# MB2_B1.net
KiCad netlist of a schematic drawn in EasyEDA Pro
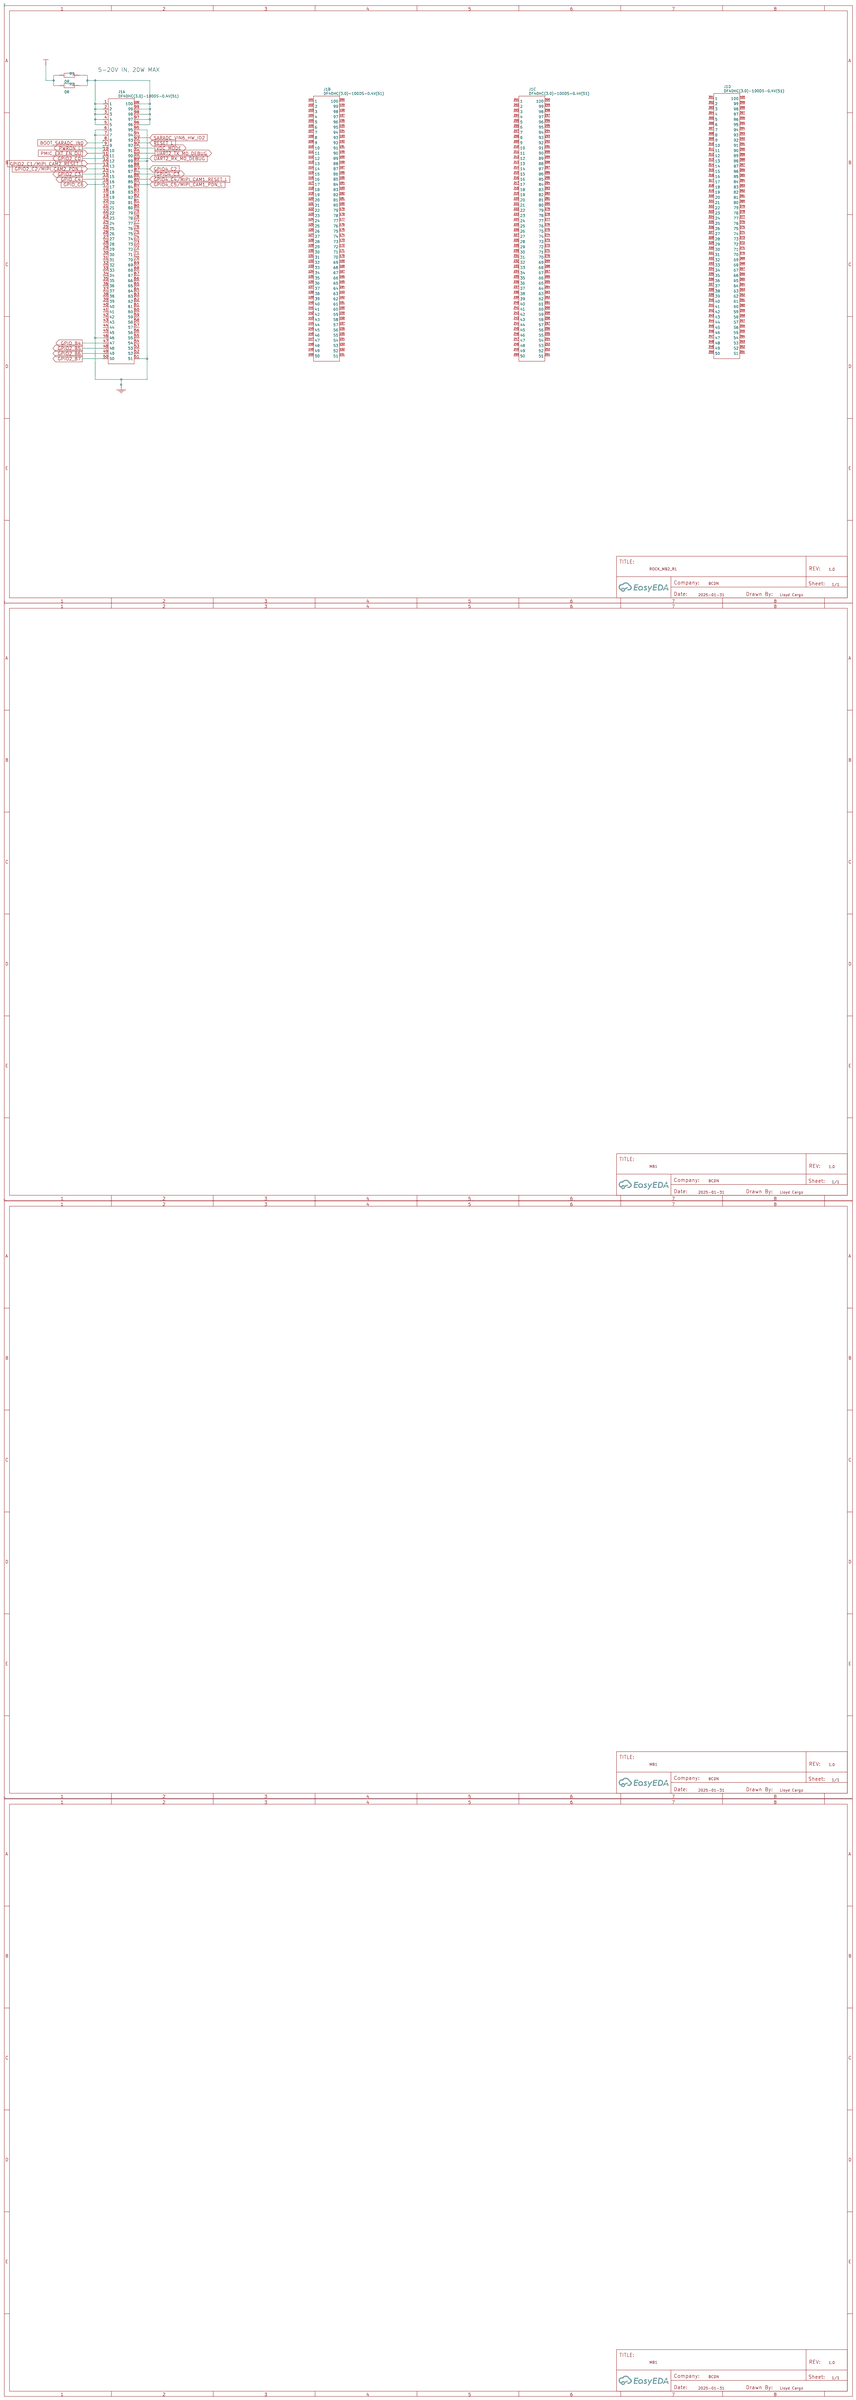
[diagram p0: schematic sheet]

(export (version "E")
  (design (tool "Eeschema 10.0.6"))
  (components
    (comp (ref "J1A")
      (value "DF40HC(3.0)-100DS-0.4V(51)")
      (fields (field (name "Manufacturer") "HRS(广濑)"))
      (libsource (lib "") (part "DF40HC(3.0)-100DS-0.4V(51)_2"))
    )
    (comp (ref "J1B")
      (value "DF40HC(3.0)-100DS-0.4V(51)")
      (fields (field (name "Manufacturer") "HRS(广濑)"))
      (libsource (lib "") (part "DF40HC(3.0)-100DS-0.4V(51)_1"))
    )
    (comp (ref "J1C")
      (value "DF40HC(3.0)-100DS-0.4V(51)")
      (fields (field (name "Manufacturer") "HRS(广濑)"))
      (libsource (lib "easyedapro") (part "DF40HC(3.0)-100DS-0.4V(51)"))
    )
    (comp (ref "J1D")
      (value "DF40HC(3.0)-100DS-0.4V(51)")
      (fields (field (name "Manufacturer") "HRS(广濑)"))
      (libsource (lib "") (part "DF40HC(3.0)-100DS-0.4V(51)_3"))
    )
    (comp (ref "R1") (value "0R") (footprint "easyedapro:R0603") (libsource (lib "easyedapro") (part "Res")))
    (comp (ref "R2") (value "0R") (footprint "easyedapro:R0603") (libsource (lib "easyedapro") (part "Res")))
  )
  (nets
    (net (code "1") (name "BOOT_SARADC_IN0") (class "Default")
      (node (ref "J1A") (pin "8") (pinfunction "8_8") (pintype "unspecified"))
    )
    (net (code "2") (name "GND") (class "Default")
      (node (ref "J1A") (pin "46") (pinfunction "46_46") (pintype "unspecified"))
      (node (ref "J1A") (pin "51") (pinfunction "51_51") (pintype "unspecified"))
      (node (ref "J1A") (pin "6") (pinfunction "6_6") (pintype "unspecified"))
      (node (ref "J1A") (pin "7") (pinfunction "7_7") (pintype "unspecified"))
      (node (ref "J1A") (pin "89") (pinfunction "89_89") (pintype "unspecified"))
      (node (ref "J1A") (pin "95") (pinfunction "95_95") (pintype "unspecified"))
    )
    (net (code "3") (name "GPIO2_B5") (class "Default")
      (node (ref "J1A") (pin "48") (pinfunction "48_48") (pintype "unspecified"))
    )
    (net (code "4") (name "GPIO2_B6") (class "Default")
      (node (ref "J1A") (pin "49") (pinfunction "49_49") (pintype "unspecified"))
    )
    (net (code "5") (name "GPIO2_B7") (class "Default")
      (node (ref "J1A") (pin "50") (pinfunction "50_50") (pintype "unspecified"))
    )
    (net (code "6") (name "GPIO2_C0") (class "Default")
      (node (ref "J1A") (pin "11") (pinfunction "11_11") (pintype "unspecified"))
    )
    (net (code "7") (name "GPIO2_C1{slash}MIPI_CAM2_RESET_L") (class "Default")
      (node (ref "J1A") (pin "12") (pinfunction "12_12") (pintype "unspecified"))
    )
    (net (code "8") (name "GPIO2_C2{slash}MIPI_CAM2_PDN_L") (class "Default")
      (node (ref "J1A") (pin "13") (pinfunction "13_13") (pintype "unspecified"))
    )
    (net (code "9") (name "GPIO2_C3") (class "Default")
      (node (ref "J1A") (pin "14") (pinfunction "14_14") (pintype "unspecified"))
    )
    (net (code "10") (name "GPIO4_C2") (class "Default")
      (node (ref "J1A") (pin "88") (pinfunction "88_88") (pintype "unspecified"))
    )
    (net (code "11") (name "GPIO4_C3") (class "Default")
      (node (ref "J1A") (pin "87") (pinfunction "87_87") (pintype "unspecified"))
    )
    (net (code "12") (name "GPIO4_C4{slash}MIPI_CAM1_RESET_L") (class "Default")
      (node (ref "J1A") (pin "86") (pinfunction "86_86") (pintype "unspecified"))
    )
    (net (code "13") (name "GPIO4_C5{slash}MIPI_CAM1_PDN_L") (class "Default")
      (node (ref "J1A") (pin "85") (pinfunction "85_85") (pintype "unspecified"))
    )
    (net (code "14") (name "GPIO_B4") (class "Default")
      (node (ref "J1A") (pin "47") (pinfunction "47_47") (pintype "unspecified"))
    )
    (net (code "15") (name "GPIO_C4") (class "Default")
      (node (ref "J1A") (pin "15") (pinfunction "15_15") (pintype "unspecified"))
    )
    (net (code "16") (name "GPIO_C6") (class "Default")
      (node (ref "J1A") (pin "16") (pinfunction "16_16") (pintype "unspecified"))
    )
    (net (code "17") (name "Net-(J1A-Pad1)") (class "Default")
      (node (ref "J1A") (pin "1") (pinfunction "1_1") (pintype "unspecified"))
      (node (ref "J1A") (pin "100") (pinfunction "100_100") (pintype "unspecified"))
      (node (ref "J1A") (pin "2") (pinfunction "2_2") (pintype "unspecified"))
      (node (ref "J1A") (pin "3") (pinfunction "3_3") (pintype "unspecified"))
      (node (ref "J1A") (pin "4") (pinfunction "4_4") (pintype "unspecified"))
      (node (ref "J1A") (pin "5") (pinfunction "5_5") (pintype "unspecified"))
      (node (ref "J1A") (pin "96") (pinfunction "96_96") (pintype "unspecified"))
      (node (ref "J1A") (pin "97") (pinfunction "97_97") (pintype "unspecified"))
      (node (ref "J1A") (pin "98") (pinfunction "98_98") (pintype "unspecified"))
      (node (ref "J1A") (pin "99") (pinfunction "99_99") (pintype "unspecified"))
      (node (ref "R1") (pin "2") (pinfunction "2_2") (pintype "input"))
      (node (ref "R2") (pin "2") (pinfunction "2_2") (pintype "input"))
    )
    (net (code "18") (name "PMIC_EXT_EN_OUT") (class "Default")
      (node (ref "J1A") (pin "10") (pinfunction "10_10") (pintype "unspecified"))
    )
    (net (code "19") (name "PWRON_L") (class "Default")
      (node (ref "J1A") (pin "9") (pinfunction "9_9") (pintype "unspecified"))
    )
    (net (code "20") (name "RESET_L") (class "Default")
      (node (ref "J1A") (pin "93") (pinfunction "93_93") (pintype "unspecified"))
    )
    (net (code "21") (name "SARADC_VIN6_HW_ID2") (class "Default")
      (node (ref "J1A") (pin "94") (pinfunction "94_94") (pintype "unspecified"))
    )
    (net (code "22") (name "UART2_RX_M0_DEBUG") (class "Default")
      (node (ref "J1A") (pin "90") (pinfunction "90_90") (pintype "unspecified"))
    )
    (net (code "23") (name "UART2_TX_M0_DEBUG") (class "Default")
      (node (ref "J1A") (pin "91") (pinfunction "91_91") (pintype "unspecified"))
    )
    (net (code "24") (name "VDC_MODE") (class "Default")
      (node (ref "J1A") (pin "92") (pinfunction "92_92") (pintype "unspecified"))
    )
    (net (code "25") (name "VDD_12V") (class "Default")
      (node (ref "R1") (pin "1") (pinfunction "1_1") (pintype "input"))
      (node (ref "R2") (pin "1") (pinfunction "1_1") (pintype "input"))
    )
    (net (code "26") (name "unconnected-(J1A-Pad17)") (class "Default")
      (node (ref "J1A") (pin "17") (pinfunction "17_17") (pintype "unspecified"))
    )
    (net (code "27") (name "unconnected-(J1A-Pad18)") (class "Default")
      (node (ref "J1A") (pin "18") (pinfunction "18_18") (pintype "unspecified"))
    )
    (net (code "28") (name "unconnected-(J1A-Pad19)") (class "Default")
      (node (ref "J1A") (pin "19") (pinfunction "19_19") (pintype "unspecified"))
    )
    (net (code "29") (name "unconnected-(J1A-Pad20)") (class "Default")
      (node (ref "J1A") (pin "20") (pinfunction "20_20") (pintype "unspecified"))
    )
    (net (code "30") (name "unconnected-(J1A-Pad21)") (class "Default")
      (node (ref "J1A") (pin "21") (pinfunction "21_21") (pintype "unspecified"))
    )
    (net (code "31") (name "unconnected-(J1A-Pad22)") (class "Default")
      (node (ref "J1A") (pin "22") (pinfunction "22_22") (pintype "unspecified"))
    )
    (net (code "32") (name "unconnected-(J1A-Pad23)") (class "Default")
      (node (ref "J1A") (pin "23") (pinfunction "23_23") (pintype "unspecified"))
    )
    (net (code "33") (name "unconnected-(J1A-Pad24)") (class "Default")
      (node (ref "J1A") (pin "24") (pinfunction "24_24") (pintype "unspecified"))
    )
    (net (code "34") (name "unconnected-(J1A-Pad25)") (class "Default")
      (node (ref "J1A") (pin "25") (pinfunction "25_25") (pintype "unspecified"))
    )
    (net (code "35") (name "unconnected-(J1A-Pad26)") (class "Default")
      (node (ref "J1A") (pin "26") (pinfunction "26_26") (pintype "unspecified"))
    )
    (net (code "36") (name "unconnected-(J1A-Pad27)") (class "Default")
      (node (ref "J1A") (pin "27") (pinfunction "27_27") (pintype "unspecified"))
    )
    (net (code "37") (name "unconnected-(J1A-Pad28)") (class "Default")
      (node (ref "J1A") (pin "28") (pinfunction "28_28") (pintype "unspecified"))
    )
    (net (code "38") (name "unconnected-(J1A-Pad29)") (class "Default")
      (node (ref "J1A") (pin "29") (pinfunction "29_29") (pintype "unspecified"))
    )
    (net (code "39") (name "unconnected-(J1A-Pad30)") (class "Default")
      (node (ref "J1A") (pin "30") (pinfunction "30_30") (pintype "unspecified"))
    )
    (net (code "40") (name "unconnected-(J1A-Pad31)") (class "Default")
      (node (ref "J1A") (pin "31") (pinfunction "31_31") (pintype "unspecified"))
    )
    (net (code "41") (name "unconnected-(J1A-Pad32)") (class "Default")
      (node (ref "J1A") (pin "32") (pinfunction "32_32") (pintype "unspecified"))
    )
    (net (code "42") (name "unconnected-(J1A-Pad33)") (class "Default")
      (node (ref "J1A") (pin "33") (pinfunction "33_33") (pintype "unspecified"))
    )
    (net (code "43") (name "unconnected-(J1A-Pad34)") (class "Default")
      (node (ref "J1A") (pin "34") (pinfunction "34_34") (pintype "unspecified"))
    )
    (net (code "44") (name "unconnected-(J1A-Pad35)") (class "Default")
      (node (ref "J1A") (pin "35") (pinfunction "35_35") (pintype "unspecified"))
    )
    (net (code "45") (name "unconnected-(J1A-Pad36)") (class "Default")
      (node (ref "J1A") (pin "36") (pinfunction "36_36") (pintype "unspecified"))
    )
    (net (code "46") (name "unconnected-(J1A-Pad37)") (class "Default")
      (node (ref "J1A") (pin "37") (pinfunction "37_37") (pintype "unspecified"))
    )
    (net (code "47") (name "unconnected-(J1A-Pad38)") (class "Default")
      (node (ref "J1A") (pin "38") (pinfunction "38_38") (pintype "unspecified"))
    )
    (net (code "48") (name "unconnected-(J1A-Pad39)") (class "Default")
      (node (ref "J1A") (pin "39") (pinfunction "39_39") (pintype "unspecified"))
    )
    (net (code "49") (name "unconnected-(J1A-Pad40)") (class "Default")
      (node (ref "J1A") (pin "40") (pinfunction "40_40") (pintype "unspecified"))
    )
    (net (code "50") (name "unconnected-(J1A-Pad41)") (class "Default")
      (node (ref "J1A") (pin "41") (pinfunction "41_41") (pintype "unspecified"))
    )
    (net (code "51") (name "unconnected-(J1A-Pad42)") (class "Default")
      (node (ref "J1A") (pin "42") (pinfunction "42_42") (pintype "unspecified"))
    )
    (net (code "52") (name "unconnected-(J1A-Pad43)") (class "Default")
      (node (ref "J1A") (pin "43") (pinfunction "43_43") (pintype "unspecified"))
    )
    (net (code "53") (name "unconnected-(J1A-Pad44)") (class "Default")
      (node (ref "J1A") (pin "44") (pinfunction "44_44") (pintype "unspecified"))
    )
    (net (code "54") (name "unconnected-(J1A-Pad45)") (class "Default")
      (node (ref "J1A") (pin "45") (pinfunction "45_45") (pintype "unspecified"))
    )
    (net (code "55") (name "unconnected-(J1A-Pad52)") (class "Default")
      (node (ref "J1A") (pin "52") (pinfunction "52_52") (pintype "unspecified"))
    )
    (net (code "56") (name "unconnected-(J1A-Pad53)") (class "Default")
      (node (ref "J1A") (pin "53") (pinfunction "53_53") (pintype "unspecified"))
    )
    (net (code "57") (name "unconnected-(J1A-Pad54)") (class "Default")
      (node (ref "J1A") (pin "54") (pinfunction "54_54") (pintype "unspecified"))
    )
    (net (code "58") (name "unconnected-(J1A-Pad55)") (class "Default")
      (node (ref "J1A") (pin "55") (pinfunction "55_55") (pintype "unspecified"))
    )
    (net (code "59") (name "unconnected-(J1A-Pad56)") (class "Default")
      (node (ref "J1A") (pin "56") (pinfunction "56_56") (pintype "unspecified"))
    )
    (net (code "60") (name "unconnected-(J1A-Pad57)") (class "Default")
      (node (ref "J1A") (pin "57") (pinfunction "57_57") (pintype "unspecified"))
    )
    (net (code "61") (name "unconnected-(J1A-Pad58)") (class "Default")
      (node (ref "J1A") (pin "58") (pinfunction "58_58") (pintype "unspecified"))
    )
    (net (code "62") (name "unconnected-(J1A-Pad59)") (class "Default")
      (node (ref "J1A") (pin "59") (pinfunction "59_59") (pintype "unspecified"))
    )
    (net (code "63") (name "unconnected-(J1A-Pad60)") (class "Default")
      (node (ref "J1A") (pin "60") (pinfunction "60_60") (pintype "unspecified"))
    )
    (net (code "64") (name "unconnected-(J1A-Pad61)") (class "Default")
      (node (ref "J1A") (pin "61") (pinfunction "61_61") (pintype "unspecified"))
    )
    (net (code "65") (name "unconnected-(J1A-Pad62)") (class "Default")
      (node (ref "J1A") (pin "62") (pinfunction "62_62") (pintype "unspecified"))
    )
    (net (code "66") (name "unconnected-(J1A-Pad63)") (class "Default")
      (node (ref "J1A") (pin "63") (pinfunction "63_63") (pintype "unspecified"))
    )
    (net (code "67") (name "unconnected-(J1A-Pad64)") (class "Default")
      (node (ref "J1A") (pin "64") (pinfunction "64_64") (pintype "unspecified"))
    )
    (net (code "68") (name "unconnected-(J1A-Pad65)") (class "Default")
      (node (ref "J1A") (pin "65") (pinfunction "65_65") (pintype "unspecified"))
    )
    (net (code "69") (name "unconnected-(J1A-Pad66)") (class "Default")
      (node (ref "J1A") (pin "66") (pinfunction "66_66") (pintype "unspecified"))
    )
    (net (code "70") (name "unconnected-(J1A-Pad67)") (class "Default")
      (node (ref "J1A") (pin "67") (pinfunction "67_67") (pintype "unspecified"))
    )
    (net (code "71") (name "unconnected-(J1A-Pad68)") (class "Default")
      (node (ref "J1A") (pin "68") (pinfunction "68_68") (pintype "unspecified"))
    )
    (net (code "72") (name "unconnected-(J1A-Pad69)") (class "Default")
      (node (ref "J1A") (pin "69") (pinfunction "69_69") (pintype "unspecified"))
    )
    (net (code "73") (name "unconnected-(J1A-Pad70)") (class "Default")
      (node (ref "J1A") (pin "70") (pinfunction "70_70") (pintype "unspecified"))
    )
    (net (code "74") (name "unconnected-(J1A-Pad71)") (class "Default")
      (node (ref "J1A") (pin "71") (pinfunction "71_71") (pintype "unspecified"))
    )
    (net (code "75") (name "unconnected-(J1A-Pad72)") (class "Default")
      (node (ref "J1A") (pin "72") (pinfunction "72_72") (pintype "unspecified"))
    )
    (net (code "76") (name "unconnected-(J1A-Pad73)") (class "Default")
      (node (ref "J1A") (pin "73") (pinfunction "73_73") (pintype "unspecified"))
    )
    (net (code "77") (name "unconnected-(J1A-Pad74)") (class "Default")
      (node (ref "J1A") (pin "74") (pinfunction "74_74") (pintype "unspecified"))
    )
    (net (code "78") (name "unconnected-(J1A-Pad75)") (class "Default")
      (node (ref "J1A") (pin "75") (pinfunction "75_75") (pintype "unspecified"))
    )
    (net (code "79") (name "unconnected-(J1A-Pad76)") (class "Default")
      (node (ref "J1A") (pin "76") (pinfunction "76_76") (pintype "unspecified"))
    )
    (net (code "80") (name "unconnected-(J1A-Pad77)") (class "Default")
      (node (ref "J1A") (pin "77") (pinfunction "77_77") (pintype "unspecified"))
    )
    (net (code "81") (name "unconnected-(J1A-Pad78)") (class "Default")
      (node (ref "J1A") (pin "78") (pinfunction "78_78") (pintype "unspecified"))
    )
    (net (code "82") (name "unconnected-(J1A-Pad79)") (class "Default")
      (node (ref "J1A") (pin "79") (pinfunction "79_79") (pintype "unspecified"))
    )
    (net (code "83") (name "unconnected-(J1A-Pad80)") (class "Default")
      (node (ref "J1A") (pin "80") (pinfunction "80_80") (pintype "unspecified"))
    )
    (net (code "84") (name "unconnected-(J1A-Pad81)") (class "Default")
      (node (ref "J1A") (pin "81") (pinfunction "81_81") (pintype "unspecified"))
    )
    (net (code "85") (name "unconnected-(J1A-Pad82)") (class "Default")
      (node (ref "J1A") (pin "82") (pinfunction "82_82") (pintype "unspecified"))
    )
    (net (code "86") (name "unconnected-(J1A-Pad83)") (class "Default")
      (node (ref "J1A") (pin "83") (pinfunction "83_83") (pintype "unspecified"))
    )
    (net (code "87") (name "unconnected-(J1A-Pad84)") (class "Default")
      (node (ref "J1A") (pin "84") (pinfunction "84_84") (pintype "unspecified"))
    )
    (net (code "88") (name "unconnected-(J1B-1-Pad101)") (class "Default")
      (node (ref "J1B") (pin "101") (pinfunction "1_101") (pintype "unspecified"))
    )
    (net (code "89") (name "unconnected-(J1B-2-Pad102)") (class "Default")
      (node (ref "J1B") (pin "102") (pinfunction "2_102") (pintype "unspecified"))
    )
    (net (code "90") (name "unconnected-(J1B-3-Pad103)") (class "Default")
      (node (ref "J1B") (pin "103") (pinfunction "3_103") (pintype "unspecified"))
    )
    (net (code "91") (name "unconnected-(J1B-4-Pad104)") (class "Default")
      (node (ref "J1B") (pin "104") (pinfunction "4_104") (pintype "unspecified"))
    )
    (net (code "92") (name "unconnected-(J1B-5-Pad105)") (class "Default")
      (node (ref "J1B") (pin "105") (pinfunction "5_105") (pintype "unspecified"))
    )
    (net (code "93") (name "unconnected-(J1B-6-Pad106)") (class "Default")
      (node (ref "J1B") (pin "106") (pinfunction "6_106") (pintype "unspecified"))
    )
    (net (code "94") (name "unconnected-(J1B-7-Pad107)") (class "Default")
      (node (ref "J1B") (pin "107") (pinfunction "7_107") (pintype "unspecified"))
    )
    (net (code "95") (name "unconnected-(J1B-8-Pad108)") (class "Default")
      (node (ref "J1B") (pin "108") (pinfunction "8_108") (pintype "unspecified"))
    )
    (net (code "96") (name "unconnected-(J1B-9-Pad109)") (class "Default")
      (node (ref "J1B") (pin "109") (pinfunction "9_109") (pintype "unspecified"))
    )
    (net (code "97") (name "unconnected-(J1B-10-Pad110)") (class "Default")
      (node (ref "J1B") (pin "110") (pinfunction "10_110") (pintype "unspecified"))
    )
    (net (code "98") (name "unconnected-(J1B-11-Pad111)") (class "Default")
      (node (ref "J1B") (pin "111") (pinfunction "11_111") (pintype "unspecified"))
    )
    (net (code "99") (name "unconnected-(J1B-12-Pad112)") (class "Default")
      (node (ref "J1B") (pin "112") (pinfunction "12_112") (pintype "unspecified"))
    )
    (net (code "100") (name "unconnected-(J1B-13-Pad113)") (class "Default")
      (node (ref "J1B") (pin "113") (pinfunction "13_113") (pintype "unspecified"))
    )
    (net (code "101") (name "unconnected-(J1B-14-Pad114)") (class "Default")
      (node (ref "J1B") (pin "114") (pinfunction "14_114") (pintype "unspecified"))
    )
    (net (code "102") (name "unconnected-(J1B-15-Pad115)") (class "Default")
      (node (ref "J1B") (pin "115") (pinfunction "15_115") (pintype "unspecified"))
    )
    (net (code "103") (name "unconnected-(J1B-16-Pad116)") (class "Default")
      (node (ref "J1B") (pin "116") (pinfunction "16_116") (pintype "unspecified"))
    )
    (net (code "104") (name "unconnected-(J1B-17-Pad117)") (class "Default")
      (node (ref "J1B") (pin "117") (pinfunction "17_117") (pintype "unspecified"))
    )
    (net (code "105") (name "unconnected-(J1B-18-Pad118)") (class "Default")
      (node (ref "J1B") (pin "118") (pinfunction "18_118") (pintype "unspecified"))
    )
    (net (code "106") (name "unconnected-(J1B-19-Pad119)") (class "Default")
      (node (ref "J1B") (pin "119") (pinfunction "19_119") (pintype "unspecified"))
    )
    (net (code "107") (name "unconnected-(J1B-20-Pad120)") (class "Default")
      (node (ref "J1B") (pin "120") (pinfunction "20_120") (pintype "unspecified"))
    )
    (net (code "108") (name "unconnected-(J1B-21-Pad121)") (class "Default")
      (node (ref "J1B") (pin "121") (pinfunction "21_121") (pintype "unspecified"))
    )
    (net (code "109") (name "unconnected-(J1B-22-Pad122)") (class "Default")
      (node (ref "J1B") (pin "122") (pinfunction "22_122") (pintype "unspecified"))
    )
    (net (code "110") (name "unconnected-(J1B-23-Pad123)") (class "Default")
      (node (ref "J1B") (pin "123") (pinfunction "23_123") (pintype "unspecified"))
    )
    (net (code "111") (name "unconnected-(J1B-24-Pad124)") (class "Default")
      (node (ref "J1B") (pin "124") (pinfunction "24_124") (pintype "unspecified"))
    )
    (net (code "112") (name "unconnected-(J1B-25-Pad125)") (class "Default")
      (node (ref "J1B") (pin "125") (pinfunction "25_125") (pintype "unspecified"))
    )
    (net (code "113") (name "unconnected-(J1B-26-Pad126)") (class "Default")
      (node (ref "J1B") (pin "126") (pinfunction "26_126") (pintype "unspecified"))
    )
    (net (code "114") (name "unconnected-(J1B-27-Pad127)") (class "Default")
      (node (ref "J1B") (pin "127") (pinfunction "27_127") (pintype "unspecified"))
    )
    (net (code "115") (name "unconnected-(J1B-28-Pad128)") (class "Default")
      (node (ref "J1B") (pin "128") (pinfunction "28_128") (pintype "unspecified"))
    )
    (net (code "116") (name "unconnected-(J1B-29-Pad129)") (class "Default")
      (node (ref "J1B") (pin "129") (pinfunction "29_129") (pintype "unspecified"))
    )
    (net (code "117") (name "unconnected-(J1B-30-Pad130)") (class "Default")
      (node (ref "J1B") (pin "130") (pinfunction "30_130") (pintype "unspecified"))
    )
    (net (code "118") (name "unconnected-(J1B-31-Pad131)") (class "Default")
      (node (ref "J1B") (pin "131") (pinfunction "31_131") (pintype "unspecified"))
    )
    (net (code "119") (name "unconnected-(J1B-32-Pad132)") (class "Default")
      (node (ref "J1B") (pin "132") (pinfunction "32_132") (pintype "unspecified"))
    )
    (net (code "120") (name "unconnected-(J1B-33-Pad133)") (class "Default")
      (node (ref "J1B") (pin "133") (pinfunction "33_133") (pintype "unspecified"))
    )
    (net (code "121") (name "unconnected-(J1B-34-Pad134)") (class "Default")
      (node (ref "J1B") (pin "134") (pinfunction "34_134") (pintype "unspecified"))
    )
    (net (code "122") (name "unconnected-(J1B-35-Pad135)") (class "Default")
      (node (ref "J1B") (pin "135") (pinfunction "35_135") (pintype "unspecified"))
    )
    (net (code "123") (name "unconnected-(J1B-36-Pad136)") (class "Default")
      (node (ref "J1B") (pin "136") (pinfunction "36_136") (pintype "unspecified"))
    )
    (net (code "124") (name "unconnected-(J1B-37-Pad137)") (class "Default")
      (node (ref "J1B") (pin "137") (pinfunction "37_137") (pintype "unspecified"))
    )
    (net (code "125") (name "unconnected-(J1B-38-Pad138)") (class "Default")
      (node (ref "J1B") (pin "138") (pinfunction "38_138") (pintype "unspecified"))
    )
    (net (code "126") (name "unconnected-(J1B-39-Pad139)") (class "Default")
      (node (ref "J1B") (pin "139") (pinfunction "39_139") (pintype "unspecified"))
    )
    (net (code "127") (name "unconnected-(J1B-40-Pad140)") (class "Default")
      (node (ref "J1B") (pin "140") (pinfunction "40_140") (pintype "unspecified"))
    )
    (net (code "128") (name "unconnected-(J1B-41-Pad141)") (class "Default")
      (node (ref "J1B") (pin "141") (pinfunction "41_141") (pintype "unspecified"))
    )
    (net (code "129") (name "unconnected-(J1B-42-Pad142)") (class "Default")
      (node (ref "J1B") (pin "142") (pinfunction "42_142") (pintype "unspecified"))
    )
    (net (code "130") (name "unconnected-(J1B-43-Pad143)") (class "Default")
      (node (ref "J1B") (pin "143") (pinfunction "43_143") (pintype "unspecified"))
    )
    (net (code "131") (name "unconnected-(J1B-44-Pad144)") (class "Default")
      (node (ref "J1B") (pin "144") (pinfunction "44_144") (pintype "unspecified"))
    )
    (net (code "132") (name "unconnected-(J1B-45-Pad145)") (class "Default")
      (node (ref "J1B") (pin "145") (pinfunction "45_145") (pintype "unspecified"))
    )
    (net (code "133") (name "unconnected-(J1B-46-Pad146)") (class "Default")
      (node (ref "J1B") (pin "146") (pinfunction "46_146") (pintype "unspecified"))
    )
    (net (code "134") (name "unconnected-(J1B-47-Pad147)") (class "Default")
      (node (ref "J1B") (pin "147") (pinfunction "47_147") (pintype "unspecified"))
    )
    (net (code "135") (name "unconnected-(J1B-48-Pad148)") (class "Default")
      (node (ref "J1B") (pin "148") (pinfunction "48_148") (pintype "unspecified"))
    )
    (net (code "136") (name "unconnected-(J1B-49-Pad149)") (class "Default")
      (node (ref "J1B") (pin "149") (pinfunction "49_149") (pintype "unspecified"))
    )
    (net (code "137") (name "unconnected-(J1B-50-Pad150)") (class "Default")
      (node (ref "J1B") (pin "150") (pinfunction "50_150") (pintype "unspecified"))
    )
    (net (code "138") (name "unconnected-(J1B-51-Pad151)") (class "Default")
      (node (ref "J1B") (pin "151") (pinfunction "51_151") (pintype "unspecified"))
    )
    (net (code "139") (name "unconnected-(J1B-52-Pad152)") (class "Default")
      (node (ref "J1B") (pin "152") (pinfunction "52_152") (pintype "unspecified"))
    )
    (net (code "140") (name "unconnected-(J1B-53-Pad153)") (class "Default")
      (node (ref "J1B") (pin "153") (pinfunction "53_153") (pintype "unspecified"))
    )
    (net (code "141") (name "unconnected-(J1B-54-Pad154)") (class "Default")
      (node (ref "J1B") (pin "154") (pinfunction "54_154") (pintype "unspecified"))
    )
    (net (code "142") (name "unconnected-(J1B-55-Pad155)") (class "Default")
      (node (ref "J1B") (pin "155") (pinfunction "55_155") (pintype "unspecified"))
    )
    (net (code "143") (name "unconnected-(J1B-56-Pad156)") (class "Default")
      (node (ref "J1B") (pin "156") (pinfunction "56_156") (pintype "unspecified"))
    )
    (net (code "144") (name "unconnected-(J1B-57-Pad157)") (class "Default")
      (node (ref "J1B") (pin "157") (pinfunction "57_157") (pintype "unspecified"))
    )
    (net (code "145") (name "unconnected-(J1B-58-Pad158)") (class "Default")
      (node (ref "J1B") (pin "158") (pinfunction "58_158") (pintype "unspecified"))
    )
    (net (code "146") (name "unconnected-(J1B-59-Pad159)") (class "Default")
      (node (ref "J1B") (pin "159") (pinfunction "59_159") (pintype "unspecified"))
    )
    (net (code "147") (name "unconnected-(J1B-60-Pad160)") (class "Default")
      (node (ref "J1B") (pin "160") (pinfunction "60_160") (pintype "unspecified"))
    )
    (net (code "148") (name "unconnected-(J1B-61-Pad161)") (class "Default")
      (node (ref "J1B") (pin "161") (pinfunction "61_161") (pintype "unspecified"))
    )
    (net (code "149") (name "unconnected-(J1B-62-Pad162)") (class "Default")
      (node (ref "J1B") (pin "162") (pinfunction "62_162") (pintype "unspecified"))
    )
    (net (code "150") (name "unconnected-(J1B-63-Pad163)") (class "Default")
      (node (ref "J1B") (pin "163") (pinfunction "63_163") (pintype "unspecified"))
    )
    (net (code "151") (name "unconnected-(J1B-64-Pad164)") (class "Default")
      (node (ref "J1B") (pin "164") (pinfunction "64_164") (pintype "unspecified"))
    )
    (net (code "152") (name "unconnected-(J1B-65-Pad165)") (class "Default")
      (node (ref "J1B") (pin "165") (pinfunction "65_165") (pintype "unspecified"))
    )
    (net (code "153") (name "unconnected-(J1B-66-Pad166)") (class "Default")
      (node (ref "J1B") (pin "166") (pinfunction "66_166") (pintype "unspecified"))
    )
    (net (code "154") (name "unconnected-(J1B-67-Pad167)") (class "Default")
      (node (ref "J1B") (pin "167") (pinfunction "67_167") (pintype "unspecified"))
    )
    (net (code "155") (name "unconnected-(J1B-68-Pad168)") (class "Default")
      (node (ref "J1B") (pin "168") (pinfunction "68_168") (pintype "unspecified"))
    )
    (net (code "156") (name "unconnected-(J1B-69-Pad169)") (class "Default")
      (node (ref "J1B") (pin "169") (pinfunction "69_169") (pintype "unspecified"))
    )
    (net (code "157") (name "unconnected-(J1B-70-Pad170)") (class "Default")
      (node (ref "J1B") (pin "170") (pinfunction "70_170") (pintype "unspecified"))
    )
    (net (code "158") (name "unconnected-(J1B-71-Pad171)") (class "Default")
      (node (ref "J1B") (pin "171") (pinfunction "71_171") (pintype "unspecified"))
    )
    (net (code "159") (name "unconnected-(J1B-72-Pad172)") (class "Default")
      (node (ref "J1B") (pin "172") (pinfunction "72_172") (pintype "unspecified"))
    )
    (net (code "160") (name "unconnected-(J1B-73-Pad173)") (class "Default")
      (node (ref "J1B") (pin "173") (pinfunction "73_173") (pintype "unspecified"))
    )
    (net (code "161") (name "unconnected-(J1B-74-Pad174)") (class "Default")
      (node (ref "J1B") (pin "174") (pinfunction "74_174") (pintype "unspecified"))
    )
    (net (code "162") (name "unconnected-(J1B-75-Pad175)") (class "Default")
      (node (ref "J1B") (pin "175") (pinfunction "75_175") (pintype "unspecified"))
    )
    (net (code "163") (name "unconnected-(J1B-76-Pad176)") (class "Default")
      (node (ref "J1B") (pin "176") (pinfunction "76_176") (pintype "unspecified"))
    )
    (net (code "164") (name "unconnected-(J1B-77-Pad177)") (class "Default")
      (node (ref "J1B") (pin "177") (pinfunction "77_177") (pintype "unspecified"))
    )
    (net (code "165") (name "unconnected-(J1B-78-Pad178)") (class "Default")
      (node (ref "J1B") (pin "178") (pinfunction "78_178") (pintype "unspecified"))
    )
    (net (code "166") (name "unconnected-(J1B-79-Pad179)") (class "Default")
      (node (ref "J1B") (pin "179") (pinfunction "79_179") (pintype "unspecified"))
    )
    (net (code "167") (name "unconnected-(J1B-80-Pad180)") (class "Default")
      (node (ref "J1B") (pin "180") (pinfunction "80_180") (pintype "unspecified"))
    )
    (net (code "168") (name "unconnected-(J1B-81-Pad181)") (class "Default")
      (node (ref "J1B") (pin "181") (pinfunction "81_181") (pintype "unspecified"))
    )
    (net (code "169") (name "unconnected-(J1B-82-Pad182)") (class "Default")
      (node (ref "J1B") (pin "182") (pinfunction "82_182") (pintype "unspecified"))
    )
    (net (code "170") (name "unconnected-(J1B-83-Pad183)") (class "Default")
      (node (ref "J1B") (pin "183") (pinfunction "83_183") (pintype "unspecified"))
    )
    (net (code "171") (name "unconnected-(J1B-84-Pad184)") (class "Default")
      (node (ref "J1B") (pin "184") (pinfunction "84_184") (pintype "unspecified"))
    )
    (net (code "172") (name "unconnected-(J1B-85-Pad185)") (class "Default")
      (node (ref "J1B") (pin "185") (pinfunction "85_185") (pintype "unspecified"))
    )
    (net (code "173") (name "unconnected-(J1B-86-Pad186)") (class "Default")
      (node (ref "J1B") (pin "186") (pinfunction "86_186") (pintype "unspecified"))
    )
    (net (code "174") (name "unconnected-(J1B-87-Pad187)") (class "Default")
      (node (ref "J1B") (pin "187") (pinfunction "87_187") (pintype "unspecified"))
    )
    (net (code "175") (name "unconnected-(J1B-88-Pad188)") (class "Default")
      (node (ref "J1B") (pin "188") (pinfunction "88_188") (pintype "unspecified"))
    )
    (net (code "176") (name "unconnected-(J1B-89-Pad189)") (class "Default")
      (node (ref "J1B") (pin "189") (pinfunction "89_189") (pintype "unspecified"))
    )
    (net (code "177") (name "unconnected-(J1B-90-Pad190)") (class "Default")
      (node (ref "J1B") (pin "190") (pinfunction "90_190") (pintype "unspecified"))
    )
    (net (code "178") (name "unconnected-(J1B-91-Pad191)") (class "Default")
      (node (ref "J1B") (pin "191") (pinfunction "91_191") (pintype "unspecified"))
    )
    (net (code "179") (name "unconnected-(J1B-92-Pad192)") (class "Default")
      (node (ref "J1B") (pin "192") (pinfunction "92_192") (pintype "unspecified"))
    )
    (net (code "180") (name "unconnected-(J1B-93-Pad193)") (class "Default")
      (node (ref "J1B") (pin "193") (pinfunction "93_193") (pintype "unspecified"))
    )
    (net (code "181") (name "unconnected-(J1B-94-Pad194)") (class "Default")
      (node (ref "J1B") (pin "194") (pinfunction "94_194") (pintype "unspecified"))
    )
    (net (code "182") (name "unconnected-(J1B-95-Pad195)") (class "Default")
      (node (ref "J1B") (pin "195") (pinfunction "95_195") (pintype "unspecified"))
    )
    (net (code "183") (name "unconnected-(J1B-96-Pad196)") (class "Default")
      (node (ref "J1B") (pin "196") (pinfunction "96_196") (pintype "unspecified"))
    )
    (net (code "184") (name "unconnected-(J1B-97-Pad197)") (class "Default")
      (node (ref "J1B") (pin "197") (pinfunction "97_197") (pintype "unspecified"))
    )
    (net (code "185") (name "unconnected-(J1B-98-Pad198)") (class "Default")
      (node (ref "J1B") (pin "198") (pinfunction "98_198") (pintype "unspecified"))
    )
    (net (code "186") (name "unconnected-(J1B-99-Pad199)") (class "Default")
      (node (ref "J1B") (pin "199") (pinfunction "99_199") (pintype "unspecified"))
    )
    (net (code "187") (name "unconnected-(J1B-100-Pad200)") (class "Default")
      (node (ref "J1B") (pin "200") (pinfunction "100_200") (pintype "unspecified"))
    )
    (net (code "188") (name "unconnected-(J1C-1-Pad201)") (class "Default")
      (node (ref "J1C") (pin "201") (pinfunction "1_201") (pintype "unspecified"))
    )
    (net (code "189") (name "unconnected-(J1C-2-Pad202)") (class "Default")
      (node (ref "J1C") (pin "202") (pinfunction "2_202") (pintype "unspecified"))
    )
    (net (code "190") (name "unconnected-(J1C-3-Pad203)") (class "Default")
      (node (ref "J1C") (pin "203") (pinfunction "3_203") (pintype "unspecified"))
    )
    (net (code "191") (name "unconnected-(J1C-4-Pad204)") (class "Default")
      (node (ref "J1C") (pin "204") (pinfunction "4_204") (pintype "unspecified"))
    )
    (net (code "192") (name "unconnected-(J1C-5-Pad205)") (class "Default")
      (node (ref "J1C") (pin "205") (pinfunction "5_205") (pintype "unspecified"))
    )
    (net (code "193") (name "unconnected-(J1C-6-Pad206)") (class "Default")
      (node (ref "J1C") (pin "206") (pinfunction "6_206") (pintype "unspecified"))
    )
    (net (code "194") (name "unconnected-(J1C-7-Pad207)") (class "Default")
      (node (ref "J1C") (pin "207") (pinfunction "7_207") (pintype "unspecified"))
    )
    (net (code "195") (name "unconnected-(J1C-8-Pad208)") (class "Default")
      (node (ref "J1C") (pin "208") (pinfunction "8_208") (pintype "unspecified"))
    )
    (net (code "196") (name "unconnected-(J1C-9-Pad209)") (class "Default")
      (node (ref "J1C") (pin "209") (pinfunction "9_209") (pintype "unspecified"))
    )
    (net (code "197") (name "unconnected-(J1C-10-Pad210)") (class "Default")
      (node (ref "J1C") (pin "210") (pinfunction "10_210") (pintype "unspecified"))
    )
    (net (code "198") (name "unconnected-(J1C-11-Pad211)") (class "Default")
      (node (ref "J1C") (pin "211") (pinfunction "11_211") (pintype "unspecified"))
    )
    (net (code "199") (name "unconnected-(J1C-12-Pad212)") (class "Default")
      (node (ref "J1C") (pin "212") (pinfunction "12_212") (pintype "unspecified"))
    )
    (net (code "200") (name "unconnected-(J1C-13-Pad213)") (class "Default")
      (node (ref "J1C") (pin "213") (pinfunction "13_213") (pintype "unspecified"))
    )
    (net (code "201") (name "unconnected-(J1C-14-Pad214)") (class "Default")
      (node (ref "J1C") (pin "214") (pinfunction "14_214") (pintype "unspecified"))
    )
    (net (code "202") (name "unconnected-(J1C-15-Pad215)") (class "Default")
      (node (ref "J1C") (pin "215") (pinfunction "15_215") (pintype "unspecified"))
    )
    (net (code "203") (name "unconnected-(J1C-16-Pad216)") (class "Default")
      (node (ref "J1C") (pin "216") (pinfunction "16_216") (pintype "unspecified"))
    )
    (net (code "204") (name "unconnected-(J1C-17-Pad217)") (class "Default")
      (node (ref "J1C") (pin "217") (pinfunction "17_217") (pintype "unspecified"))
    )
    (net (code "205") (name "unconnected-(J1C-18-Pad218)") (class "Default")
      (node (ref "J1C") (pin "218") (pinfunction "18_218") (pintype "unspecified"))
    )
    (net (code "206") (name "unconnected-(J1C-19-Pad219)") (class "Default")
      (node (ref "J1C") (pin "219") (pinfunction "19_219") (pintype "unspecified"))
    )
    (net (code "207") (name "unconnected-(J1C-20-Pad220)") (class "Default")
      (node (ref "J1C") (pin "220") (pinfunction "20_220") (pintype "unspecified"))
    )
    (net (code "208") (name "unconnected-(J1C-21-Pad221)") (class "Default")
      (node (ref "J1C") (pin "221") (pinfunction "21_221") (pintype "unspecified"))
    )
    (net (code "209") (name "unconnected-(J1C-22-Pad222)") (class "Default")
      (node (ref "J1C") (pin "222") (pinfunction "22_222") (pintype "unspecified"))
    )
    (net (code "210") (name "unconnected-(J1C-23-Pad223)") (class "Default")
      (node (ref "J1C") (pin "223") (pinfunction "23_223") (pintype "unspecified"))
    )
    (net (code "211") (name "unconnected-(J1C-24-Pad224)") (class "Default")
      (node (ref "J1C") (pin "224") (pinfunction "24_224") (pintype "unspecified"))
    )
    (net (code "212") (name "unconnected-(J1C-25-Pad225)") (class "Default")
      (node (ref "J1C") (pin "225") (pinfunction "25_225") (pintype "unspecified"))
    )
    (net (code "213") (name "unconnected-(J1C-26-Pad226)") (class "Default")
      (node (ref "J1C") (pin "226") (pinfunction "26_226") (pintype "unspecified"))
    )
    (net (code "214") (name "unconnected-(J1C-27-Pad227)") (class "Default")
      (node (ref "J1C") (pin "227") (pinfunction "27_227") (pintype "unspecified"))
    )
    (net (code "215") (name "unconnected-(J1C-28-Pad228)") (class "Default")
      (node (ref "J1C") (pin "228") (pinfunction "28_228") (pintype "unspecified"))
    )
    (net (code "216") (name "unconnected-(J1C-29-Pad229)") (class "Default")
      (node (ref "J1C") (pin "229") (pinfunction "29_229") (pintype "unspecified"))
    )
    (net (code "217") (name "unconnected-(J1C-30-Pad230)") (class "Default")
      (node (ref "J1C") (pin "230") (pinfunction "30_230") (pintype "unspecified"))
    )
    (net (code "218") (name "unconnected-(J1C-31-Pad231)") (class "Default")
      (node (ref "J1C") (pin "231") (pinfunction "31_231") (pintype "unspecified"))
    )
    (net (code "219") (name "unconnected-(J1C-32-Pad232)") (class "Default")
      (node (ref "J1C") (pin "232") (pinfunction "32_232") (pintype "unspecified"))
    )
    (net (code "220") (name "unconnected-(J1C-33-Pad233)") (class "Default")
      (node (ref "J1C") (pin "233") (pinfunction "33_233") (pintype "unspecified"))
    )
    (net (code "221") (name "unconnected-(J1C-34-Pad234)") (class "Default")
      (node (ref "J1C") (pin "234") (pinfunction "34_234") (pintype "unspecified"))
    )
    (net (code "222") (name "unconnected-(J1C-35-Pad235)") (class "Default")
      (node (ref "J1C") (pin "235") (pinfunction "35_235") (pintype "unspecified"))
    )
    (net (code "223") (name "unconnected-(J1C-36-Pad236)") (class "Default")
      (node (ref "J1C") (pin "236") (pinfunction "36_236") (pintype "unspecified"))
    )
    (net (code "224") (name "unconnected-(J1C-37-Pad237)") (class "Default")
      (node (ref "J1C") (pin "237") (pinfunction "37_237") (pintype "unspecified"))
    )
    (net (code "225") (name "unconnected-(J1C-38-Pad238)") (class "Default")
      (node (ref "J1C") (pin "238") (pinfunction "38_238") (pintype "unspecified"))
    )
    (net (code "226") (name "unconnected-(J1C-39-Pad239)") (class "Default")
      (node (ref "J1C") (pin "239") (pinfunction "39_239") (pintype "unspecified"))
    )
    (net (code "227") (name "unconnected-(J1C-40-Pad240)") (class "Default")
      (node (ref "J1C") (pin "240") (pinfunction "40_240") (pintype "unspecified"))
    )
    (net (code "228") (name "unconnected-(J1C-41-Pad241)") (class "Default")
      (node (ref "J1C") (pin "241") (pinfunction "41_241") (pintype "unspecified"))
    )
    (net (code "229") (name "unconnected-(J1C-42-Pad242)") (class "Default")
      (node (ref "J1C") (pin "242") (pinfunction "42_242") (pintype "unspecified"))
    )
    (net (code "230") (name "unconnected-(J1C-43-Pad243)") (class "Default")
      (node (ref "J1C") (pin "243") (pinfunction "43_243") (pintype "unspecified"))
    )
    (net (code "231") (name "unconnected-(J1C-44-Pad244)") (class "Default")
      (node (ref "J1C") (pin "244") (pinfunction "44_244") (pintype "unspecified"))
    )
    (net (code "232") (name "unconnected-(J1C-45-Pad245)") (class "Default")
      (node (ref "J1C") (pin "245") (pinfunction "45_245") (pintype "unspecified"))
    )
    (net (code "233") (name "unconnected-(J1C-46-Pad246)") (class "Default")
      (node (ref "J1C") (pin "246") (pinfunction "46_246") (pintype "unspecified"))
    )
    (net (code "234") (name "unconnected-(J1C-47-Pad247)") (class "Default")
      (node (ref "J1C") (pin "247") (pinfunction "47_247") (pintype "unspecified"))
    )
    (net (code "235") (name "unconnected-(J1C-48-Pad248)") (class "Default")
      (node (ref "J1C") (pin "248") (pinfunction "48_248") (pintype "unspecified"))
    )
    (net (code "236") (name "unconnected-(J1C-49-Pad249)") (class "Default")
      (node (ref "J1C") (pin "249") (pinfunction "49_249") (pintype "unspecified"))
    )
    (net (code "237") (name "unconnected-(J1C-50-Pad250)") (class "Default")
      (node (ref "J1C") (pin "250") (pinfunction "50_250") (pintype "unspecified"))
    )
    (net (code "238") (name "unconnected-(J1C-51-Pad251)") (class "Default")
      (node (ref "J1C") (pin "251") (pinfunction "51_251") (pintype "unspecified"))
    )
    (net (code "239") (name "unconnected-(J1C-52-Pad252)") (class "Default")
      (node (ref "J1C") (pin "252") (pinfunction "52_252") (pintype "unspecified"))
    )
    (net (code "240") (name "unconnected-(J1C-53-Pad253)") (class "Default")
      (node (ref "J1C") (pin "253") (pinfunction "53_253") (pintype "unspecified"))
    )
    (net (code "241") (name "unconnected-(J1C-54-Pad254)") (class "Default")
      (node (ref "J1C") (pin "254") (pinfunction "54_254") (pintype "unspecified"))
    )
    (net (code "242") (name "unconnected-(J1C-55-Pad255)") (class "Default")
      (node (ref "J1C") (pin "255") (pinfunction "55_255") (pintype "unspecified"))
    )
    (net (code "243") (name "unconnected-(J1C-56-Pad256)") (class "Default")
      (node (ref "J1C") (pin "256") (pinfunction "56_256") (pintype "unspecified"))
    )
    (net (code "244") (name "unconnected-(J1C-57-Pad257)") (class "Default")
      (node (ref "J1C") (pin "257") (pinfunction "57_257") (pintype "unspecified"))
    )
    (net (code "245") (name "unconnected-(J1C-58-Pad258)") (class "Default")
      (node (ref "J1C") (pin "258") (pinfunction "58_258") (pintype "unspecified"))
    )
    (net (code "246") (name "unconnected-(J1C-59-Pad259)") (class "Default")
      (node (ref "J1C") (pin "259") (pinfunction "59_259") (pintype "unspecified"))
    )
    (net (code "247") (name "unconnected-(J1C-60-Pad260)") (class "Default")
      (node (ref "J1C") (pin "260") (pinfunction "60_260") (pintype "unspecified"))
    )
    (net (code "248") (name "unconnected-(J1C-61-Pad261)") (class "Default")
      (node (ref "J1C") (pin "261") (pinfunction "61_261") (pintype "unspecified"))
    )
    (net (code "249") (name "unconnected-(J1C-62-Pad262)") (class "Default")
      (node (ref "J1C") (pin "262") (pinfunction "62_262") (pintype "unspecified"))
    )
    (net (code "250") (name "unconnected-(J1C-63-Pad263)") (class "Default")
      (node (ref "J1C") (pin "263") (pinfunction "63_263") (pintype "unspecified"))
    )
    (net (code "251") (name "unconnected-(J1C-64-Pad264)") (class "Default")
      (node (ref "J1C") (pin "264") (pinfunction "64_264") (pintype "unspecified"))
    )
    (net (code "252") (name "unconnected-(J1C-65-Pad265)") (class "Default")
      (node (ref "J1C") (pin "265") (pinfunction "65_265") (pintype "unspecified"))
    )
    (net (code "253") (name "unconnected-(J1C-66-Pad266)") (class "Default")
      (node (ref "J1C") (pin "266") (pinfunction "66_266") (pintype "unspecified"))
    )
    (net (code "254") (name "unconnected-(J1C-67-Pad267)") (class "Default")
      (node (ref "J1C") (pin "267") (pinfunction "67_267") (pintype "unspecified"))
    )
    (net (code "255") (name "unconnected-(J1C-68-Pad268)") (class "Default")
      (node (ref "J1C") (pin "268") (pinfunction "68_268") (pintype "unspecified"))
    )
    (net (code "256") (name "unconnected-(J1C-69-Pad269)") (class "Default")
      (node (ref "J1C") (pin "269") (pinfunction "69_269") (pintype "unspecified"))
    )
    (net (code "257") (name "unconnected-(J1C-70-Pad270)") (class "Default")
      (node (ref "J1C") (pin "270") (pinfunction "70_270") (pintype "unspecified"))
    )
    (net (code "258") (name "unconnected-(J1C-71-Pad271)") (class "Default")
      (node (ref "J1C") (pin "271") (pinfunction "71_271") (pintype "unspecified"))
    )
    (net (code "259") (name "unconnected-(J1C-72-Pad272)") (class "Default")
      (node (ref "J1C") (pin "272") (pinfunction "72_272") (pintype "unspecified"))
    )
    (net (code "260") (name "unconnected-(J1C-73-Pad273)") (class "Default")
      (node (ref "J1C") (pin "273") (pinfunction "73_273") (pintype "unspecified"))
    )
    (net (code "261") (name "unconnected-(J1C-74-Pad274)") (class "Default")
      (node (ref "J1C") (pin "274") (pinfunction "74_274") (pintype "unspecified"))
    )
    (net (code "262") (name "unconnected-(J1C-75-Pad275)") (class "Default")
      (node (ref "J1C") (pin "275") (pinfunction "75_275") (pintype "unspecified"))
    )
    (net (code "263") (name "unconnected-(J1C-76-Pad276)") (class "Default")
      (node (ref "J1C") (pin "276") (pinfunction "76_276") (pintype "unspecified"))
    )
    (net (code "264") (name "unconnected-(J1C-77-Pad277)") (class "Default")
      (node (ref "J1C") (pin "277") (pinfunction "77_277") (pintype "unspecified"))
    )
    (net (code "265") (name "unconnected-(J1C-78-Pad278)") (class "Default")
      (node (ref "J1C") (pin "278") (pinfunction "78_278") (pintype "unspecified"))
    )
    (net (code "266") (name "unconnected-(J1C-79-Pad279)") (class "Default")
      (node (ref "J1C") (pin "279") (pinfunction "79_279") (pintype "unspecified"))
    )
    (net (code "267") (name "unconnected-(J1C-80-Pad280)") (class "Default")
      (node (ref "J1C") (pin "280") (pinfunction "80_280") (pintype "unspecified"))
    )
    (net (code "268") (name "unconnected-(J1C-81-Pad281)") (class "Default")
      (node (ref "J1C") (pin "281") (pinfunction "81_281") (pintype "unspecified"))
    )
    (net (code "269") (name "unconnected-(J1C-82-Pad282)") (class "Default")
      (node (ref "J1C") (pin "282") (pinfunction "82_282") (pintype "unspecified"))
    )
    (net (code "270") (name "unconnected-(J1C-83-Pad283)") (class "Default")
      (node (ref "J1C") (pin "283") (pinfunction "83_283") (pintype "unspecified"))
    )
    (net (code "271") (name "unconnected-(J1C-84-Pad284)") (class "Default")
      (node (ref "J1C") (pin "284") (pinfunction "84_284") (pintype "unspecified"))
    )
    (net (code "272") (name "unconnected-(J1C-85-Pad285)") (class "Default")
      (node (ref "J1C") (pin "285") (pinfunction "85_285") (pintype "unspecified"))
    )
    (net (code "273") (name "unconnected-(J1C-86-Pad286)") (class "Default")
      (node (ref "J1C") (pin "286") (pinfunction "86_286") (pintype "unspecified"))
    )
    (net (code "274") (name "unconnected-(J1C-87-Pad287)") (class "Default")
      (node (ref "J1C") (pin "287") (pinfunction "87_287") (pintype "unspecified"))
    )
    (net (code "275") (name "unconnected-(J1C-88-Pad288)") (class "Default")
      (node (ref "J1C") (pin "288") (pinfunction "88_288") (pintype "unspecified"))
    )
    (net (code "276") (name "unconnected-(J1C-89-Pad289)") (class "Default")
      (node (ref "J1C") (pin "289") (pinfunction "89_289") (pintype "unspecified"))
    )
    (net (code "277") (name "unconnected-(J1C-90-Pad290)") (class "Default")
      (node (ref "J1C") (pin "290") (pinfunction "90_290") (pintype "unspecified"))
    )
    (net (code "278") (name "unconnected-(J1C-91-Pad291)") (class "Default")
      (node (ref "J1C") (pin "291") (pinfunction "91_291") (pintype "unspecified"))
    )
    (net (code "279") (name "unconnected-(J1C-92-Pad292)") (class "Default")
      (node (ref "J1C") (pin "292") (pinfunction "92_292") (pintype "unspecified"))
    )
    (net (code "280") (name "unconnected-(J1C-93-Pad293)") (class "Default")
      (node (ref "J1C") (pin "293") (pinfunction "93_293") (pintype "unspecified"))
    )
    (net (code "281") (name "unconnected-(J1C-94-Pad294)") (class "Default")
      (node (ref "J1C") (pin "294") (pinfunction "94_294") (pintype "unspecified"))
    )
    (net (code "282") (name "unconnected-(J1C-95-Pad295)") (class "Default")
      (node (ref "J1C") (pin "295") (pinfunction "95_295") (pintype "unspecified"))
    )
    (net (code "283") (name "unconnected-(J1C-96-Pad296)") (class "Default")
      (node (ref "J1C") (pin "296") (pinfunction "96_296") (pintype "unspecified"))
    )
    (net (code "284") (name "unconnected-(J1C-97-Pad297)") (class "Default")
      (node (ref "J1C") (pin "297") (pinfunction "97_297") (pintype "unspecified"))
    )
    (net (code "285") (name "unconnected-(J1C-98-Pad298)") (class "Default")
      (node (ref "J1C") (pin "298") (pinfunction "98_298") (pintype "unspecified"))
    )
    (net (code "286") (name "unconnected-(J1C-99-Pad299)") (class "Default")
      (node (ref "J1C") (pin "299") (pinfunction "99_299") (pintype "unspecified"))
    )
    (net (code "287") (name "unconnected-(J1C-100-Pad300)") (class "Default")
      (node (ref "J1C") (pin "300") (pinfunction "100_300") (pintype "unspecified"))
    )
    (net (code "288") (name "unconnected-(J1D-1-Pad301)") (class "Default")
      (node (ref "J1D") (pin "301") (pinfunction "1_301") (pintype "unspecified"))
    )
    (net (code "289") (name "unconnected-(J1D-2-Pad302)") (class "Default")
      (node (ref "J1D") (pin "302") (pinfunction "2_302") (pintype "unspecified"))
    )
    (net (code "290") (name "unconnected-(J1D-3-Pad303)") (class "Default")
      (node (ref "J1D") (pin "303") (pinfunction "3_303") (pintype "unspecified"))
    )
    (net (code "291") (name "unconnected-(J1D-4-Pad304)") (class "Default")
      (node (ref "J1D") (pin "304") (pinfunction "4_304") (pintype "unspecified"))
    )
    (net (code "292") (name "unconnected-(J1D-5-Pad305)") (class "Default")
      (node (ref "J1D") (pin "305") (pinfunction "5_305") (pintype "unspecified"))
    )
    (net (code "293") (name "unconnected-(J1D-6-Pad306)") (class "Default")
      (node (ref "J1D") (pin "306") (pinfunction "6_306") (pintype "unspecified"))
    )
    (net (code "294") (name "unconnected-(J1D-7-Pad307)") (class "Default")
      (node (ref "J1D") (pin "307") (pinfunction "7_307") (pintype "unspecified"))
    )
    (net (code "295") (name "unconnected-(J1D-8-Pad308)") (class "Default")
      (node (ref "J1D") (pin "308") (pinfunction "8_308") (pintype "unspecified"))
    )
    (net (code "296") (name "unconnected-(J1D-9-Pad309)") (class "Default")
      (node (ref "J1D") (pin "309") (pinfunction "9_309") (pintype "unspecified"))
    )
    (net (code "297") (name "unconnected-(J1D-10-Pad310)") (class "Default")
      (node (ref "J1D") (pin "310") (pinfunction "10_310") (pintype "unspecified"))
    )
    (net (code "298") (name "unconnected-(J1D-11-Pad311)") (class "Default")
      (node (ref "J1D") (pin "311") (pinfunction "11_311") (pintype "unspecified"))
    )
    (net (code "299") (name "unconnected-(J1D-12-Pad312)") (class "Default")
      (node (ref "J1D") (pin "312") (pinfunction "12_312") (pintype "unspecified"))
    )
    (net (code "300") (name "unconnected-(J1D-13-Pad313)") (class "Default")
      (node (ref "J1D") (pin "313") (pinfunction "13_313") (pintype "unspecified"))
    )
    (net (code "301") (name "unconnected-(J1D-14-Pad314)") (class "Default")
      (node (ref "J1D") (pin "314") (pinfunction "14_314") (pintype "unspecified"))
    )
    (net (code "302") (name "unconnected-(J1D-15-Pad315)") (class "Default")
      (node (ref "J1D") (pin "315") (pinfunction "15_315") (pintype "unspecified"))
    )
    (net (code "303") (name "unconnected-(J1D-16-Pad316)") (class "Default")
      (node (ref "J1D") (pin "316") (pinfunction "16_316") (pintype "unspecified"))
    )
    (net (code "304") (name "unconnected-(J1D-17-Pad317)") (class "Default")
      (node (ref "J1D") (pin "317") (pinfunction "17_317") (pintype "unspecified"))
    )
    (net (code "305") (name "unconnected-(J1D-18-Pad318)") (class "Default")
      (node (ref "J1D") (pin "318") (pinfunction "18_318") (pintype "unspecified"))
    )
    (net (code "306") (name "unconnected-(J1D-19-Pad319)") (class "Default")
      (node (ref "J1D") (pin "319") (pinfunction "19_319") (pintype "unspecified"))
    )
    (net (code "307") (name "unconnected-(J1D-20-Pad320)") (class "Default")
      (node (ref "J1D") (pin "320") (pinfunction "20_320") (pintype "unspecified"))
    )
    (net (code "308") (name "unconnected-(J1D-21-Pad321)") (class "Default")
      (node (ref "J1D") (pin "321") (pinfunction "21_321") (pintype "unspecified"))
    )
    (net (code "309") (name "unconnected-(J1D-22-Pad322)") (class "Default")
      (node (ref "J1D") (pin "322") (pinfunction "22_322") (pintype "unspecified"))
    )
    (net (code "310") (name "unconnected-(J1D-23-Pad323)") (class "Default")
      (node (ref "J1D") (pin "323") (pinfunction "23_323") (pintype "unspecified"))
    )
    (net (code "311") (name "unconnected-(J1D-24-Pad324)") (class "Default")
      (node (ref "J1D") (pin "324") (pinfunction "24_324") (pintype "unspecified"))
    )
    (net (code "312") (name "unconnected-(J1D-25-Pad325)") (class "Default")
      (node (ref "J1D") (pin "325") (pinfunction "25_325") (pintype "unspecified"))
    )
    (net (code "313") (name "unconnected-(J1D-26-Pad326)") (class "Default")
      (node (ref "J1D") (pin "326") (pinfunction "26_326") (pintype "unspecified"))
    )
    (net (code "314") (name "unconnected-(J1D-27-Pad327)") (class "Default")
      (node (ref "J1D") (pin "327") (pinfunction "27_327") (pintype "unspecified"))
    )
    (net (code "315") (name "unconnected-(J1D-28-Pad328)") (class "Default")
      (node (ref "J1D") (pin "328") (pinfunction "28_328") (pintype "unspecified"))
    )
    (net (code "316") (name "unconnected-(J1D-29-Pad329)") (class "Default")
      (node (ref "J1D") (pin "329") (pinfunction "29_329") (pintype "unspecified"))
    )
    (net (code "317") (name "unconnected-(J1D-30-Pad330)") (class "Default")
      (node (ref "J1D") (pin "330") (pinfunction "30_330") (pintype "unspecified"))
    )
    (net (code "318") (name "unconnected-(J1D-31-Pad331)") (class "Default")
      (node (ref "J1D") (pin "331") (pinfunction "31_331") (pintype "unspecified"))
    )
    (net (code "319") (name "unconnected-(J1D-32-Pad332)") (class "Default")
      (node (ref "J1D") (pin "332") (pinfunction "32_332") (pintype "unspecified"))
    )
    (net (code "320") (name "unconnected-(J1D-33-Pad333)") (class "Default")
      (node (ref "J1D") (pin "333") (pinfunction "33_333") (pintype "unspecified"))
    )
    (net (code "321") (name "unconnected-(J1D-34-Pad334)") (class "Default")
      (node (ref "J1D") (pin "334") (pinfunction "34_334") (pintype "unspecified"))
    )
    (net (code "322") (name "unconnected-(J1D-35-Pad335)") (class "Default")
      (node (ref "J1D") (pin "335") (pinfunction "35_335") (pintype "unspecified"))
    )
    (net (code "323") (name "unconnected-(J1D-36-Pad336)") (class "Default")
      (node (ref "J1D") (pin "336") (pinfunction "36_336") (pintype "unspecified"))
    )
    (net (code "324") (name "unconnected-(J1D-37-Pad337)") (class "Default")
      (node (ref "J1D") (pin "337") (pinfunction "37_337") (pintype "unspecified"))
    )
    (net (code "325") (name "unconnected-(J1D-38-Pad338)") (class "Default")
      (node (ref "J1D") (pin "338") (pinfunction "38_338") (pintype "unspecified"))
    )
    (net (code "326") (name "unconnected-(J1D-39-Pad339)") (class "Default")
      (node (ref "J1D") (pin "339") (pinfunction "39_339") (pintype "unspecified"))
    )
    (net (code "327") (name "unconnected-(J1D-40-Pad340)") (class "Default")
      (node (ref "J1D") (pin "340") (pinfunction "40_340") (pintype "unspecified"))
    )
    (net (code "328") (name "unconnected-(J1D-41-Pad341)") (class "Default")
      (node (ref "J1D") (pin "341") (pinfunction "41_341") (pintype "unspecified"))
    )
    (net (code "329") (name "unconnected-(J1D-42-Pad342)") (class "Default")
      (node (ref "J1D") (pin "342") (pinfunction "42_342") (pintype "unspecified"))
    )
    (net (code "330") (name "unconnected-(J1D-43-Pad343)") (class "Default")
      (node (ref "J1D") (pin "343") (pinfunction "43_343") (pintype "unspecified"))
    )
    (net (code "331") (name "unconnected-(J1D-44-Pad344)") (class "Default")
      (node (ref "J1D") (pin "344") (pinfunction "44_344") (pintype "unspecified"))
    )
    (net (code "332") (name "unconnected-(J1D-45-Pad345)") (class "Default")
      (node (ref "J1D") (pin "345") (pinfunction "45_345") (pintype "unspecified"))
    )
    (net (code "333") (name "unconnected-(J1D-46-Pad346)") (class "Default")
      (node (ref "J1D") (pin "346") (pinfunction "46_346") (pintype "unspecified"))
    )
    (net (code "334") (name "unconnected-(J1D-47-Pad347)") (class "Default")
      (node (ref "J1D") (pin "347") (pinfunction "47_347") (pintype "unspecified"))
    )
    (net (code "335") (name "unconnected-(J1D-48-Pad348)") (class "Default")
      (node (ref "J1D") (pin "348") (pinfunction "48_348") (pintype "unspecified"))
    )
    (net (code "336") (name "unconnected-(J1D-49-Pad349)") (class "Default")
      (node (ref "J1D") (pin "349") (pinfunction "49_349") (pintype "unspecified"))
    )
    (net (code "337") (name "unconnected-(J1D-50-Pad350)") (class "Default")
      (node (ref "J1D") (pin "350") (pinfunction "50_350") (pintype "unspecified"))
    )
    (net (code "338") (name "unconnected-(J1D-51-Pad351)") (class "Default")
      (node (ref "J1D") (pin "351") (pinfunction "51_351") (pintype "unspecified"))
    )
    (net (code "339") (name "unconnected-(J1D-52-Pad352)") (class "Default")
      (node (ref "J1D") (pin "352") (pinfunction "52_352") (pintype "unspecified"))
    )
    (net (code "340") (name "unconnected-(J1D-53-Pad353)") (class "Default")
      (node (ref "J1D") (pin "353") (pinfunction "53_353") (pintype "unspecified"))
    )
    (net (code "341") (name "unconnected-(J1D-54-Pad354)") (class "Default")
      (node (ref "J1D") (pin "354") (pinfunction "54_354") (pintype "unspecified"))
    )
    (net (code "342") (name "unconnected-(J1D-55-Pad355)") (class "Default")
      (node (ref "J1D") (pin "355") (pinfunction "55_355") (pintype "unspecified"))
    )
    (net (code "343") (name "unconnected-(J1D-56-Pad356)") (class "Default")
      (node (ref "J1D") (pin "356") (pinfunction "56_356") (pintype "unspecified"))
    )
    (net (code "344") (name "unconnected-(J1D-57-Pad357)") (class "Default")
      (node (ref "J1D") (pin "357") (pinfunction "57_357") (pintype "unspecified"))
    )
    (net (code "345") (name "unconnected-(J1D-58-Pad358)") (class "Default")
      (node (ref "J1D") (pin "358") (pinfunction "58_358") (pintype "unspecified"))
    )
    (net (code "346") (name "unconnected-(J1D-59-Pad359)") (class "Default")
      (node (ref "J1D") (pin "359") (pinfunction "59_359") (pintype "unspecified"))
    )
    (net (code "347") (name "unconnected-(J1D-60-Pad360)") (class "Default")
      (node (ref "J1D") (pin "360") (pinfunction "60_360") (pintype "unspecified"))
    )
    (net (code "348") (name "unconnected-(J1D-61-Pad361)") (class "Default")
      (node (ref "J1D") (pin "361") (pinfunction "61_361") (pintype "unspecified"))
    )
    (net (code "349") (name "unconnected-(J1D-62-Pad362)") (class "Default")
      (node (ref "J1D") (pin "362") (pinfunction "62_362") (pintype "unspecified"))
    )
    (net (code "350") (name "unconnected-(J1D-63-Pad363)") (class "Default")
      (node (ref "J1D") (pin "363") (pinfunction "63_363") (pintype "unspecified"))
    )
    (net (code "351") (name "unconnected-(J1D-64-Pad364)") (class "Default")
      (node (ref "J1D") (pin "364") (pinfunction "64_364") (pintype "unspecified"))
    )
    (net (code "352") (name "unconnected-(J1D-65-Pad365)") (class "Default")
      (node (ref "J1D") (pin "365") (pinfunction "65_365") (pintype "unspecified"))
    )
    (net (code "353") (name "unconnected-(J1D-66-Pad366)") (class "Default")
      (node (ref "J1D") (pin "366") (pinfunction "66_366") (pintype "unspecified"))
    )
    (net (code "354") (name "unconnected-(J1D-67-Pad367)") (class "Default")
      (node (ref "J1D") (pin "367") (pinfunction "67_367") (pintype "unspecified"))
    )
    (net (code "355") (name "unconnected-(J1D-68-Pad368)") (class "Default")
      (node (ref "J1D") (pin "368") (pinfunction "68_368") (pintype "unspecified"))
    )
    (net (code "356") (name "unconnected-(J1D-69-Pad369)") (class "Default")
      (node (ref "J1D") (pin "369") (pinfunction "69_369") (pintype "unspecified"))
    )
    (net (code "357") (name "unconnected-(J1D-70-Pad370)") (class "Default")
      (node (ref "J1D") (pin "370") (pinfunction "70_370") (pintype "unspecified"))
    )
    (net (code "358") (name "unconnected-(J1D-71-Pad371)") (class "Default")
      (node (ref "J1D") (pin "371") (pinfunction "71_371") (pintype "unspecified"))
    )
    (net (code "359") (name "unconnected-(J1D-72-Pad372)") (class "Default")
      (node (ref "J1D") (pin "372") (pinfunction "72_372") (pintype "unspecified"))
    )
    (net (code "360") (name "unconnected-(J1D-73-Pad373)") (class "Default")
      (node (ref "J1D") (pin "373") (pinfunction "73_373") (pintype "unspecified"))
    )
    (net (code "361") (name "unconnected-(J1D-74-Pad374)") (class "Default")
      (node (ref "J1D") (pin "374") (pinfunction "74_374") (pintype "unspecified"))
    )
    (net (code "362") (name "unconnected-(J1D-75-Pad375)") (class "Default")
      (node (ref "J1D") (pin "375") (pinfunction "75_375") (pintype "unspecified"))
    )
    (net (code "363") (name "unconnected-(J1D-76-Pad376)") (class "Default")
      (node (ref "J1D") (pin "376") (pinfunction "76_376") (pintype "unspecified"))
    )
    (net (code "364") (name "unconnected-(J1D-77-Pad377)") (class "Default")
      (node (ref "J1D") (pin "377") (pinfunction "77_377") (pintype "unspecified"))
    )
    (net (code "365") (name "unconnected-(J1D-78-Pad378)") (class "Default")
      (node (ref "J1D") (pin "378") (pinfunction "78_378") (pintype "unspecified"))
    )
    (net (code "366") (name "unconnected-(J1D-79-Pad379)") (class "Default")
      (node (ref "J1D") (pin "379") (pinfunction "79_379") (pintype "unspecified"))
    )
    (net (code "367") (name "unconnected-(J1D-80-Pad380)") (class "Default")
      (node (ref "J1D") (pin "380") (pinfunction "80_380") (pintype "unspecified"))
    )
    (net (code "368") (name "unconnected-(J1D-81-Pad381)") (class "Default")
      (node (ref "J1D") (pin "381") (pinfunction "81_381") (pintype "unspecified"))
    )
    (net (code "369") (name "unconnected-(J1D-82-Pad382)") (class "Default")
      (node (ref "J1D") (pin "382") (pinfunction "82_382") (pintype "unspecified"))
    )
    (net (code "370") (name "unconnected-(J1D-83-Pad383)") (class "Default")
      (node (ref "J1D") (pin "383") (pinfunction "83_383") (pintype "unspecified"))
    )
    (net (code "371") (name "unconnected-(J1D-84-Pad384)") (class "Default")
      (node (ref "J1D") (pin "384") (pinfunction "84_384") (pintype "unspecified"))
    )
    (net (code "372") (name "unconnected-(J1D-85-Pad385)") (class "Default")
      (node (ref "J1D") (pin "385") (pinfunction "85_385") (pintype "unspecified"))
    )
    (net (code "373") (name "unconnected-(J1D-86-Pad386)") (class "Default")
      (node (ref "J1D") (pin "386") (pinfunction "86_386") (pintype "unspecified"))
    )
    (net (code "374") (name "unconnected-(J1D-87-Pad387)") (class "Default")
      (node (ref "J1D") (pin "387") (pinfunction "87_387") (pintype "unspecified"))
    )
    (net (code "375") (name "unconnected-(J1D-88-Pad388)") (class "Default")
      (node (ref "J1D") (pin "388") (pinfunction "88_388") (pintype "unspecified"))
    )
    (net (code "376") (name "unconnected-(J1D-89-Pad389)") (class "Default")
      (node (ref "J1D") (pin "389") (pinfunction "89_389") (pintype "unspecified"))
    )
    (net (code "377") (name "unconnected-(J1D-90-Pad390)") (class "Default")
      (node (ref "J1D") (pin "390") (pinfunction "90_390") (pintype "unspecified"))
    )
    (net (code "378") (name "unconnected-(J1D-91-Pad391)") (class "Default")
      (node (ref "J1D") (pin "391") (pinfunction "91_391") (pintype "unspecified"))
    )
    (net (code "379") (name "unconnected-(J1D-92-Pad392)") (class "Default")
      (node (ref "J1D") (pin "392") (pinfunction "92_392") (pintype "unspecified"))
    )
    (net (code "380") (name "unconnected-(J1D-93-Pad393)") (class "Default")
      (node (ref "J1D") (pin "393") (pinfunction "93_393") (pintype "unspecified"))
    )
    (net (code "381") (name "unconnected-(J1D-94-Pad394)") (class "Default")
      (node (ref "J1D") (pin "394") (pinfunction "94_394") (pintype "unspecified"))
    )
    (net (code "382") (name "unconnected-(J1D-95-Pad395)") (class "Default")
      (node (ref "J1D") (pin "395") (pinfunction "95_395") (pintype "unspecified"))
    )
    (net (code "383") (name "unconnected-(J1D-96-Pad396)") (class "Default")
      (node (ref "J1D") (pin "396") (pinfunction "96_396") (pintype "unspecified"))
    )
    (net (code "384") (name "unconnected-(J1D-97-Pad397)") (class "Default")
      (node (ref "J1D") (pin "397") (pinfunction "97_397") (pintype "unspecified"))
    )
    (net (code "385") (name "unconnected-(J1D-98-Pad398)") (class "Default")
      (node (ref "J1D") (pin "398") (pinfunction "98_398") (pintype "unspecified"))
    )
    (net (code "386") (name "unconnected-(J1D-99-Pad399)") (class "Default")
      (node (ref "J1D") (pin "399") (pinfunction "99_399") (pintype "unspecified"))
    )
    (net (code "387") (name "unconnected-(J1D-100-Pad400)") (class "Default")
      (node (ref "J1D") (pin "400") (pinfunction "100_400") (pintype "unspecified"))
    )
  )
)
